# R2P_DCM_module.net
KiCad netlist of a schematic drawn in EAGLE
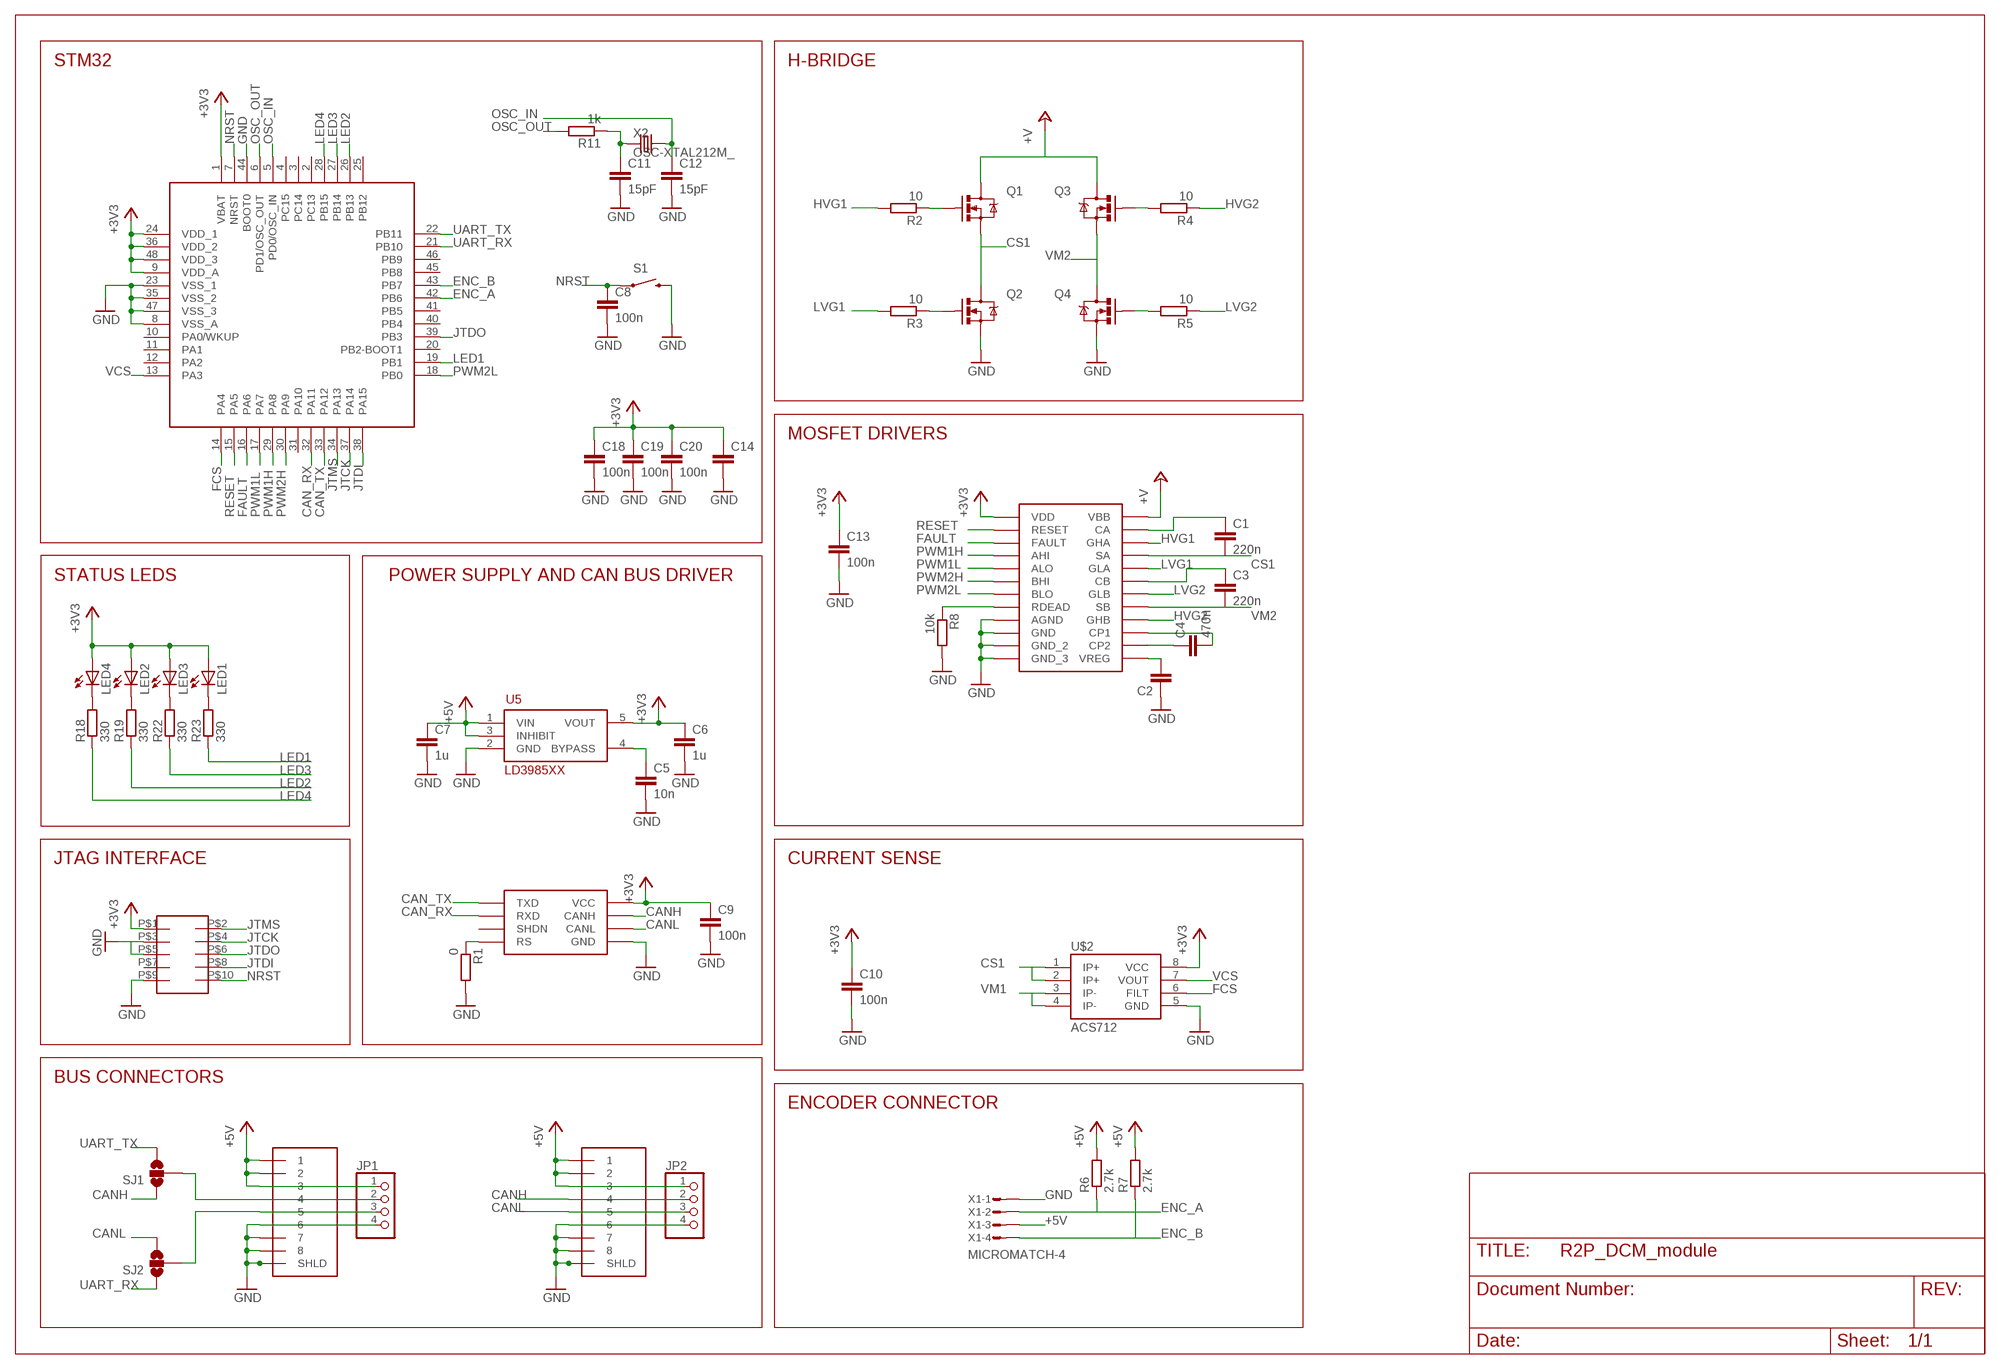
[diagram p0: schematic, sheet 1]

(export (version "E")
  (design (tool "Eeschema 10.0.6"))
  (components
    (comp (ref "1")
      (value "RJ45-43860")
      (footprint "eagle-import:0438600010")
      (libsource (lib "eagle-import") (part "RJ45-43860"))
    )
    (comp (ref "2")
      (value "RJ45-43860")
      (footprint "eagle-import:0438600010")
      (libsource (lib "eagle-import") (part "RJ45-43860"))
    )
    (comp (ref "C1")
      (value "220n")
      (footprint "eagle-import:C0603")
      (libsource (lib "eagle-import") (part "C-EUC0603"))
    )
    (comp (ref "C2")
      (value "C-EUC0805")
      (footprint "eagle-import:C0805")
      (libsource (lib "eagle-import") (part "C-EUC0805"))
    )
    (comp (ref "C3")
      (value "220n")
      (footprint "eagle-import:C0603")
      (libsource (lib "eagle-import") (part "C-EUC0603"))
    )
    (comp (ref "C4")
      (value "470n")
      (footprint "eagle-import:C0603")
      (libsource (lib "eagle-import") (part "C-EUC0603"))
    )
    (comp (ref "C5")
      (value "10n")
      (footprint "eagle-import:C0603")
      (libsource (lib "eagle-import") (part "C-EUC0603"))
    )
    (comp (ref "C6")
      (value "1u")
      (footprint "eagle-import:C0603")
      (libsource (lib "eagle-import") (part "C-EUC0603"))
    )
    (comp (ref "C7")
      (value "1u")
      (footprint "eagle-import:C0603")
      (libsource (lib "eagle-import") (part "C-EUC0603"))
    )
    (comp (ref "C8")
      (value "100n")
      (footprint "eagle-import:C0603")
      (libsource (lib "eagle-import") (part "C-EUC0603"))
    )
    (comp (ref "C9")
      (value "100n")
      (footprint "eagle-import:C0603")
      (libsource (lib "eagle-import") (part "C-EUC0603"))
    )
    (comp (ref "C10")
      (value "100n")
      (footprint "eagle-import:C0603")
      (libsource (lib "eagle-import") (part "C-EUC0603"))
    )
    (comp (ref "C11")
      (value "15pF")
      (footprint "eagle-import:C0603")
      (libsource (lib "eagle-import") (part "C-EUC0603"))
    )
    (comp (ref "C12")
      (value "15pF")
      (footprint "eagle-import:C0603")
      (libsource (lib "eagle-import") (part "C-EUC0603"))
    )
    (comp (ref "C13")
      (value "100n")
      (footprint "eagle-import:C0603")
      (libsource (lib "eagle-import") (part "C-EUC0603"))
    )
    (comp (ref "C14")
      (value "C-EUC0805")
      (footprint "eagle-import:C0805")
      (libsource (lib "eagle-import") (part "C-EUC0805"))
    )
    (comp (ref "C18")
      (value "100n")
      (footprint "eagle-import:C0603")
      (libsource (lib "eagle-import") (part "C-EUC0603"))
    )
    (comp (ref "C19")
      (value "100n")
      (footprint "eagle-import:C0603")
      (libsource (lib "eagle-import") (part "C-EUC0603"))
    )
    (comp (ref "C20")
      (value "100n")
      (footprint "eagle-import:C0603")
      (libsource (lib "eagle-import") (part "C-EUC0603"))
    )
    (comp (ref "JP1")
      (value "PINHD-1X4/90")
      (footprint "eagle-import:1X04_90")
      (libsource (lib "eagle-import") (part "PINHD-1X4/90"))
    )
    (comp (ref "JP2")
      (value "PINHD-1X4/90")
      (footprint "eagle-import:1X04_90")
      (libsource (lib "eagle-import") (part "PINHD-1X4/90"))
    )
    (comp (ref "LED1")
      (value "LEDCHIPLED_0805")
      (footprint "eagle-import:CHIPLED_0805")
      (libsource (lib "eagle-import") (part "LEDCHIPLED_0805"))
    )
    (comp (ref "LED2")
      (value "LEDCHIPLED_0805")
      (footprint "eagle-import:CHIPLED_0805")
      (libsource (lib "eagle-import") (part "LEDCHIPLED_0805"))
    )
    (comp (ref "LED3")
      (value "LEDCHIPLED_0805")
      (footprint "eagle-import:CHIPLED_0805")
      (libsource (lib "eagle-import") (part "LEDCHIPLED_0805"))
    )
    (comp (ref "LED4")
      (value "LEDCHIPLED_0805")
      (footprint "eagle-import:CHIPLED_0805")
      (libsource (lib "eagle-import") (part "LEDCHIPLED_0805"))
    )
    (comp (ref "Q1")
      (value "MOSFET-NCHANNELFDD8580")
      (footprint "eagle-import:DPAK")
      (libsource (lib "eagle-import") (part "MOSFET-NCHANNELFDD8580"))
    )
    (comp (ref "Q2")
      (value "MOSFET-NCHANNELFDD8580")
      (footprint "eagle-import:DPAK")
      (libsource (lib "eagle-import") (part "MOSFET-NCHANNELFDD8580"))
    )
    (comp (ref "Q3")
      (value "MOSFET-NCHANNELFDD8580")
      (footprint "eagle-import:DPAK")
      (libsource (lib "eagle-import") (part "MOSFET-NCHANNELFDD8580"))
    )
    (comp (ref "Q4")
      (value "MOSFET-NCHANNELFDD8580")
      (footprint "eagle-import:DPAK")
      (libsource (lib "eagle-import") (part "MOSFET-NCHANNELFDD8580"))
    )
    (comp (ref "R1")
      (value "0")
      (footprint "eagle-import:R0603")
      (libsource (lib "eagle-import") (part "R-EU_R0603"))
    )
    (comp (ref "R2")
      (value "10")
      (footprint "eagle-import:R0603")
      (libsource (lib "eagle-import") (part "R-EU_R0603"))
    )
    (comp (ref "R3")
      (value "10")
      (footprint "eagle-import:R0603")
      (libsource (lib "eagle-import") (part "R-EU_R0603"))
    )
    (comp (ref "R4")
      (value "10")
      (footprint "eagle-import:R0603")
      (libsource (lib "eagle-import") (part "R-EU_R0603"))
    )
    (comp (ref "R5")
      (value "10")
      (footprint "eagle-import:R0603")
      (libsource (lib "eagle-import") (part "R-EU_R0603"))
    )
    (comp (ref "R6")
      (value "2.7k")
      (footprint "eagle-import:R0603")
      (libsource (lib "eagle-import") (part "R-EU_R0603"))
    )
    (comp (ref "R7")
      (value "2.7k")
      (footprint "eagle-import:R0603")
      (libsource (lib "eagle-import") (part "R-EU_R0603"))
    )
    (comp (ref "R8")
      (value "10k")
      (footprint "eagle-import:R0603")
      (libsource (lib "eagle-import") (part "R-EU_R0603"))
    )
    (comp (ref "R11")
      (value "1k")
      (footprint "eagle-import:R0603")
      (libsource (lib "eagle-import") (part "R-EU_R0603"))
    )
    (comp (ref "R18")
      (value "330")
      (footprint "eagle-import:R0603")
      (libsource (lib "eagle-import") (part "R-EU_R0603"))
    )
    (comp (ref "R19")
      (value "330")
      (footprint "eagle-import:R0603")
      (libsource (lib "eagle-import") (part "R-EU_R0603"))
    )
    (comp (ref "R22")
      (value "330")
      (footprint "eagle-import:R0603")
      (libsource (lib "eagle-import") (part "R-EU_R0603"))
    )
    (comp (ref "R23")
      (value "330")
      (footprint "eagle-import:R0603")
      (libsource (lib "eagle-import") (part "R-EU_R0603"))
    )
    (comp (ref "S1")
      (value "SWITCH-MOMENTARY-2-SMD-1101NE")
      (footprint "eagle-import:TACTILE-SWITCH-1101NE")
      (libsource (lib "eagle-import") (part "SWITCH-MOMENTARY-2-SMD-1101NE"))
    )
    (comp (ref "SJ1")
      (value "SOLDERJUMPER_2WAYPASTE1&2")
      (footprint "eagle-import:SJ_3_PASTE1&2")
      (libsource (lib "eagle-import") (part "SOLDERJUMPER_2WAYPASTE1&2"))
    )
    (comp (ref "SJ2")
      (value "SOLDERJUMPER_2WAYPASTE1&2")
      (footprint "eagle-import:SJ_3_PASTE1&2")
      (libsource (lib "eagle-import") (part "SOLDERJUMPER_2WAYPASTE1&2"))
    )
    (comp (ref "SOT1")
      (value "MAX3051")
      (footprint "eagle-import:SOT23-8L")
      (libsource (lib "eagle-import") (part "MAX3051"))
    )
    (comp (ref "U$1")
      (value "A4940")
      (footprint "eagle-import:TSSOP24")
      (libsource (lib "eagle-import") (part "A4940"))
    )
    (comp (ref "U$2")
      (value "ACS712")
      (footprint "eagle-import:SO08")
      (libsource (lib "eagle-import") (part "ACS712"))
    )
    (comp (ref "U$4")
      (value "FTSH-105")
      (footprint "eagle-import:FTSH-105")
      (libsource (lib "eagle-import") (part "FTSH-105"))
    )
    (comp (ref "U1")
      (value "STM32F103CX")
      (footprint "eagle-import:LQFP48")
      (libsource (lib "eagle-import") (part "STM32F103CX"))
    )
    (comp (ref "U5")
      (value "LD3985XX")
      (footprint "eagle-import:SOT23-5L")
      (libsource (lib "eagle-import") (part "LD3985XX"))
    )
    (comp (ref "X1")
      (value "MICROMATCH-4")
      (footprint "eagle-import:MICROMATCH-4")
      (libsource (lib "eagle-import") (part "MICROMATCH-4"))
    )
    (comp (ref "X2")
      (value "OSC-XTAL212M_")
      (footprint "eagle-import:4X6")
      (libsource (lib "eagle-import") (part "OSC-XTAL212M_"))
    )
  )
  (nets
    (net (code "1") (name "+3V3") (class "Default")
      (node (ref "C10") (pin "1") (pinfunction "1_1") (pintype "passive"))
      (node (ref "C13") (pin "1") (pinfunction "1_1") (pintype "passive"))
      (node (ref "C14") (pin "1") (pinfunction "1_1") (pintype "passive"))
      (node (ref "C18") (pin "1") (pinfunction "1_1") (pintype "passive"))
      (node (ref "C19") (pin "1") (pinfunction "1_1") (pintype "passive"))
      (node (ref "C20") (pin "1") (pinfunction "1_1") (pintype "passive"))
      (node (ref "C6") (pin "1") (pinfunction "1_1") (pintype "passive"))
      (node (ref "C9") (pin "1") (pinfunction "1_1") (pintype "passive"))
      (node (ref "LED1") (pin "A") (pinfunction "A_A") (pintype "passive"))
      (node (ref "LED2") (pin "A") (pinfunction "A_A") (pintype "passive"))
      (node (ref "LED3") (pin "A") (pinfunction "A_A") (pintype "passive"))
      (node (ref "LED4") (pin "A") (pinfunction "A_A") (pintype "passive"))
      (node (ref "SOT1") (pin "P$3") (pinfunction "VCC_P$3") (pintype "bidirectional"))
      (node (ref "U$1") (pin "21") (pinfunction "VDD_21") (pintype "bidirectional"))
      (node (ref "U$2") (pin "8") (pinfunction "VCC_8") (pintype "bidirectional"))
      (node (ref "U$4") (pin "P$1") (pinfunction "P$1_P$1") (pintype "bidirectional"))
      (node (ref "U1") (pin "1") (pinfunction "VBAT_1") (pintype "bidirectional"))
      (node (ref "U1") (pin "24") (pinfunction "VDD_1_24") (pintype "bidirectional"))
      (node (ref "U1") (pin "36") (pinfunction "VDD_2_36") (pintype "bidirectional"))
      (node (ref "U1") (pin "48") (pinfunction "VDD_3_48") (pintype "bidirectional"))
      (node (ref "U1") (pin "9") (pinfunction "VDD_A_9") (pintype "bidirectional"))
      (node (ref "U5") (pin "5") (pinfunction "VOUT_5") (pintype "bidirectional"))
    )
    (net (code "2") (name "+5V") (class "Default")
      (node (ref "1") (pin "P$1") (pinfunction "1_P$1") (pintype "bidirectional"))
      (node (ref "1") (pin "P$2") (pinfunction "2_P$2") (pintype "bidirectional"))
      (node (ref "1") (pin "P$3") (pinfunction "3_P$3") (pintype "bidirectional"))
      (node (ref "2") (pin "P$1") (pinfunction "1_P$1") (pintype "bidirectional"))
      (node (ref "2") (pin "P$2") (pinfunction "2_P$2") (pintype "bidirectional"))
      (node (ref "2") (pin "P$3") (pinfunction "3_P$3") (pintype "bidirectional"))
      (node (ref "C7") (pin "1") (pinfunction "1_1") (pintype "passive"))
      (node (ref "JP1") (pin "1") (pinfunction "1_1") (pintype "passive"))
      (node (ref "JP2") (pin "1") (pinfunction "1_1") (pintype "passive"))
      (node (ref "R6") (pin "2") (pinfunction "2_2") (pintype "passive"))
      (node (ref "R7") (pin "2") (pinfunction "2_2") (pintype "passive"))
      (node (ref "U5") (pin "1") (pinfunction "VIN_1") (pintype "bidirectional"))
      (node (ref "U5") (pin "3") (pinfunction "INHIBIT_3") (pintype "bidirectional"))
      (node (ref "X1") (pin "3") (pinfunction "S_3") (pintype "passive"))
    )
    (net (code "3") (name "+V") (class "Default")
      (node (ref "Q1") (pin "4") (pinfunction "D_4") (pintype "passive"))
      (node (ref "Q3") (pin "4") (pinfunction "D_4") (pintype "passive"))
      (node (ref "U$1") (pin "12") (pinfunction "VBB_12") (pintype "bidirectional"))
    )
    (net (code "4") (name "/CANH") (class "Default")
      (node (ref "2") (pin "P$4") (pinfunction "4_P$4") (pintype "bidirectional"))
      (node (ref "JP2") (pin "2") (pinfunction "2_2") (pintype "passive"))
      (node (ref "SJ1") (pin "1") (pinfunction "1_1") (pintype "passive"))
      (node (ref "SOT1") (pin "P$7") (pinfunction "CANH_P$7") (pintype "bidirectional"))
    )
    (net (code "5") (name "/CANL") (class "Default")
      (node (ref "2") (pin "P$5") (pinfunction "5_P$5") (pintype "bidirectional"))
      (node (ref "JP2") (pin "3") (pinfunction "3_3") (pintype "passive"))
      (node (ref "SJ2") (pin "3") (pinfunction "3_3") (pintype "passive"))
      (node (ref "SOT1") (pin "P$6") (pinfunction "CANL_P$6") (pintype "bidirectional"))
    )
    (net (code "6") (name "/CAN_RX") (class "Default")
      (node (ref "SOT1") (pin "P$4") (pinfunction "RXD_P$4") (pintype "bidirectional"))
      (node (ref "U1") (pin "32") (pinfunction "PA11_32") (pintype "bidirectional"))
    )
    (net (code "7") (name "/CAN_TX") (class "Default")
      (node (ref "SOT1") (pin "P$1") (pinfunction "TXD_P$1") (pintype "bidirectional"))
      (node (ref "U1") (pin "33") (pinfunction "PA12_33") (pintype "bidirectional"))
    )
    (net (code "8") (name "/CS1") (class "Default")
      (node (ref "C1") (pin "2") (pinfunction "2_2") (pintype "passive"))
      (node (ref "Q1") (pin "3") (pinfunction "S_3") (pintype "passive"))
      (node (ref "Q2") (pin "4") (pinfunction "D_4") (pintype "passive"))
      (node (ref "U$1") (pin "10") (pinfunction "SA_10") (pintype "bidirectional"))
      (node (ref "U$2") (pin "1") (pinfunction "IP+_1") (pintype "bidirectional"))
      (node (ref "U$2") (pin "2") (pinfunction "IP+_2") (pintype "bidirectional"))
    )
    (net (code "9") (name "/ENC_A") (class "Default")
      (node (ref "R6") (pin "1") (pinfunction "1_1") (pintype "passive"))
      (node (ref "U1") (pin "42") (pinfunction "PB6_42") (pintype "bidirectional"))
      (node (ref "X1") (pin "2") (pinfunction "S_2") (pintype "passive"))
    )
    (net (code "10") (name "/ENC_B") (class "Default")
      (node (ref "R7") (pin "1") (pinfunction "1_1") (pintype "passive"))
      (node (ref "U1") (pin "43") (pinfunction "PB7_43") (pintype "bidirectional"))
      (node (ref "X1") (pin "4") (pinfunction "S_4") (pintype "passive"))
    )
    (net (code "11") (name "/FAULT") (class "Default")
      (node (ref "U$1") (pin "24") (pinfunction "FAULT_24") (pintype "bidirectional"))
      (node (ref "U1") (pin "16") (pinfunction "PA6_16") (pintype "bidirectional"))
    )
    (net (code "12") (name "/FCS") (class "Default")
      (node (ref "U$2") (pin "6") (pinfunction "FILT_6") (pintype "bidirectional"))
      (node (ref "U1") (pin "14") (pinfunction "PA4_14") (pintype "bidirectional"))
    )
    (net (code "13") (name "/HVG1") (class "Default")
      (node (ref "R2") (pin "2") (pinfunction "2_2") (pintype "passive"))
      (node (ref "U$1") (pin "9") (pinfunction "GHA_9") (pintype "bidirectional"))
    )
    (net (code "14") (name "/HVG2") (class "Default")
      (node (ref "R4") (pin "1") (pinfunction "1_1") (pintype "passive"))
      (node (ref "U$1") (pin "5") (pinfunction "GHB_5") (pintype "bidirectional"))
    )
    (net (code "15") (name "/JTCK") (class "Default")
      (node (ref "U$4") (pin "P$4") (pinfunction "P$4_P$4") (pintype "bidirectional"))
      (node (ref "U1") (pin "37") (pinfunction "PA14_37") (pintype "bidirectional"))
    )
    (net (code "16") (name "/JTDI") (class "Default")
      (node (ref "U$4") (pin "P$8") (pinfunction "P$8_P$8") (pintype "bidirectional"))
      (node (ref "U1") (pin "38") (pinfunction "PA15_38") (pintype "bidirectional"))
    )
    (net (code "17") (name "/JTDO") (class "Default")
      (node (ref "U$4") (pin "P$6") (pinfunction "P$6_P$6") (pintype "bidirectional"))
      (node (ref "U1") (pin "39") (pinfunction "PB3_39") (pintype "bidirectional"))
    )
    (net (code "18") (name "/JTMS") (class "Default")
      (node (ref "U$4") (pin "P$2") (pinfunction "P$2_P$2") (pintype "bidirectional"))
      (node (ref "U1") (pin "34") (pinfunction "PA13_34") (pintype "bidirectional"))
    )
    (net (code "19") (name "/LED1") (class "Default")
      (node (ref "R23") (pin "1") (pinfunction "1_1") (pintype "passive"))
      (node (ref "U1") (pin "19") (pinfunction "PB1_19") (pintype "bidirectional"))
    )
    (net (code "20") (name "/LED2") (class "Default")
      (node (ref "R19") (pin "1") (pinfunction "1_1") (pintype "passive"))
      (node (ref "U1") (pin "26") (pinfunction "PB13_26") (pintype "bidirectional"))
    )
    (net (code "21") (name "/LED3") (class "Default")
      (node (ref "R22") (pin "1") (pinfunction "1_1") (pintype "passive"))
      (node (ref "U1") (pin "27") (pinfunction "PB14_27") (pintype "bidirectional"))
    )
    (net (code "22") (name "/LED4") (class "Default")
      (node (ref "R18") (pin "1") (pinfunction "1_1") (pintype "passive"))
      (node (ref "U1") (pin "28") (pinfunction "PB15_28") (pintype "bidirectional"))
    )
    (net (code "23") (name "/LVG1") (class "Default")
      (node (ref "R3") (pin "2") (pinfunction "2_2") (pintype "passive"))
      (node (ref "U$1") (pin "11") (pinfunction "GLA_11") (pintype "bidirectional"))
    )
    (net (code "24") (name "/LVG2") (class "Default")
      (node (ref "R5") (pin "1") (pinfunction "1_1") (pintype "passive"))
      (node (ref "U$1") (pin "3") (pinfunction "GLB_3") (pintype "bidirectional"))
    )
    (net (code "25") (name "/NRST") (class "Default")
      (node (ref "C8") (pin "1") (pinfunction "1_1") (pintype "passive"))
      (node (ref "S1") (pin "P$1") (pinfunction "1_P$1") (pintype "passive"))
      (node (ref "U$4") (pin "P$10") (pinfunction "P$10_P$10") (pintype "bidirectional"))
      (node (ref "U1") (pin "7") (pinfunction "NRST_7") (pintype "bidirectional"))
    )
    (net (code "26") (name "/OSC_IN") (class "Default")
      (node (ref "C12") (pin "1") (pinfunction "1_1") (pintype "passive"))
      (node (ref "U1") (pin "5") (pinfunction "PD0/OSC_IN_5") (pintype "bidirectional"))
      (node (ref "X2") (pin "2") (pinfunction "X2_2") (pintype "bidirectional"))
    )
    (net (code "27") (name "/OSC_OUT") (class "Default")
      (node (ref "R11") (pin "2") (pinfunction "2_2") (pintype "passive"))
      (node (ref "U1") (pin "6") (pinfunction "PD1/OSC_OUT_6") (pintype "bidirectional"))
    )
    (net (code "28") (name "/PWM1H") (class "Default")
      (node (ref "U$1") (pin "20") (pinfunction "AHI_20") (pintype "bidirectional"))
      (node (ref "U1") (pin "29") (pinfunction "PA8_29") (pintype "bidirectional"))
    )
    (net (code "29") (name "/PWM1L") (class "Default")
      (node (ref "U$1") (pin "19") (pinfunction "ALO_19") (pintype "bidirectional"))
      (node (ref "U1") (pin "17") (pinfunction "PA7_17") (pintype "bidirectional"))
    )
    (net (code "30") (name "/PWM2H") (class "Default")
      (node (ref "U$1") (pin "18") (pinfunction "BHI_18") (pintype "bidirectional"))
      (node (ref "U1") (pin "30") (pinfunction "PA9_30") (pintype "bidirectional"))
    )
    (net (code "31") (name "/PWM2L") (class "Default")
      (node (ref "U$1") (pin "17") (pinfunction "BLO_17") (pintype "bidirectional"))
      (node (ref "U1") (pin "18") (pinfunction "PB0_18") (pintype "bidirectional"))
    )
    (net (code "32") (name "/RESET") (class "Default")
      (node (ref "U$1") (pin "1") (pinfunction "RESET_1") (pintype "bidirectional"))
      (node (ref "U1") (pin "15") (pinfunction "PA5_15") (pintype "bidirectional"))
    )
    (net (code "33") (name "/UART_RX") (class "Default")
      (node (ref "SJ2") (pin "1") (pinfunction "1_1") (pintype "passive"))
      (node (ref "U1") (pin "21") (pinfunction "PB10_21") (pintype "bidirectional"))
    )
    (net (code "34") (name "/UART_TX") (class "Default")
      (node (ref "SJ1") (pin "3") (pinfunction "3_3") (pintype "passive"))
      (node (ref "U1") (pin "22") (pinfunction "PB11_22") (pintype "bidirectional"))
    )
    (net (code "35") (name "/VCS") (class "Default")
      (node (ref "U$2") (pin "7") (pinfunction "VOUT_7") (pintype "bidirectional"))
      (node (ref "U1") (pin "13") (pinfunction "PA3_13") (pintype "bidirectional"))
    )
    (net (code "36") (name "/VM1") (class "Default")
      (node (ref "U$2") (pin "3") (pinfunction "IP-_3") (pintype "bidirectional"))
      (node (ref "U$2") (pin "4") (pinfunction "IP-_4") (pintype "bidirectional"))
    )
    (net (code "37") (name "/VM2") (class "Default")
      (node (ref "C3") (pin "2") (pinfunction "2_2") (pintype "passive"))
      (node (ref "Q3") (pin "3") (pinfunction "S_3") (pintype "passive"))
      (node (ref "Q4") (pin "4") (pinfunction "D_4") (pintype "passive"))
      (node (ref "U$1") (pin "4") (pinfunction "SB_4") (pintype "bidirectional"))
    )
    (net (code "38") (name "GND") (class "Default")
      (node (ref "1") (pin "P$10") (pinfunction "P$1_P$10") (pintype "power_in"))
      (node (ref "1") (pin "P$6") (pinfunction "6_P$6") (pintype "bidirectional"))
      (node (ref "1") (pin "P$7") (pinfunction "7_P$7") (pintype "bidirectional"))
      (node (ref "1") (pin "P$8") (pinfunction "8_P$8") (pintype "bidirectional"))
      (node (ref "1") (pin "P$9") (pinfunction "SHLD_P$9") (pintype "power_in"))
      (node (ref "2") (pin "P$10") (pinfunction "P$1_P$10") (pintype "power_in"))
      (node (ref "2") (pin "P$6") (pinfunction "6_P$6") (pintype "bidirectional"))
      (node (ref "2") (pin "P$7") (pinfunction "7_P$7") (pintype "bidirectional"))
      (node (ref "2") (pin "P$8") (pinfunction "8_P$8") (pintype "bidirectional"))
      (node (ref "2") (pin "P$9") (pinfunction "SHLD_P$9") (pintype "power_in"))
      (node (ref "C10") (pin "2") (pinfunction "2_2") (pintype "passive"))
      (node (ref "C11") (pin "2") (pinfunction "2_2") (pintype "passive"))
      (node (ref "C12") (pin "2") (pinfunction "2_2") (pintype "passive"))
      (node (ref "C13") (pin "2") (pinfunction "2_2") (pintype "passive"))
      (node (ref "C14") (pin "2") (pinfunction "2_2") (pintype "passive"))
      (node (ref "C18") (pin "2") (pinfunction "2_2") (pintype "passive"))
      (node (ref "C19") (pin "2") (pinfunction "2_2") (pintype "passive"))
      (node (ref "C2") (pin "1") (pinfunction "1_1") (pintype "passive"))
      (node (ref "C20") (pin "2") (pinfunction "2_2") (pintype "passive"))
      (node (ref "C5") (pin "2") (pinfunction "2_2") (pintype "passive"))
      (node (ref "C6") (pin "2") (pinfunction "2_2") (pintype "passive"))
      (node (ref "C7") (pin "2") (pinfunction "2_2") (pintype "passive"))
      (node (ref "C8") (pin "2") (pinfunction "2_2") (pintype "passive"))
      (node (ref "C9") (pin "2") (pinfunction "2_2") (pintype "passive"))
      (node (ref "JP1") (pin "4") (pinfunction "4_4") (pintype "passive"))
      (node (ref "JP2") (pin "4") (pinfunction "4_4") (pintype "passive"))
      (node (ref "Q2") (pin "3") (pinfunction "S_3") (pintype "passive"))
      (node (ref "Q4") (pin "3") (pinfunction "S_3") (pintype "passive"))
      (node (ref "R1") (pin "2") (pinfunction "2_2") (pintype "passive"))
      (node (ref "R8") (pin "2") (pinfunction "2_2") (pintype "passive"))
      (node (ref "S1") (pin "P$2") (pinfunction "2_P$2") (pintype "passive"))
      (node (ref "SOT1") (pin "P$2") (pinfunction "GND_P$2") (pintype "bidirectional"))
      (node (ref "U$1") (pin "15") (pinfunction "GND_2_15") (pintype "bidirectional"))
      (node (ref "U$1") (pin "16") (pinfunction "GND_3_16") (pintype "bidirectional"))
      (node (ref "U$1") (pin "2") (pinfunction "GND_2") (pintype "bidirectional"))
      (node (ref "U$1") (pin "22") (pinfunction "AGND_22") (pintype "bidirectional"))
      (node (ref "U$1") (pin "PAD") (pinfunction "GND_PAD") (pintype "bidirectional"))
      (node (ref "U$2") (pin "5") (pinfunction "GND_5") (pintype "bidirectional"))
      (node (ref "U$4") (pin "P$3") (pinfunction "P$3_P$3") (pintype "bidirectional"))
      (node (ref "U$4") (pin "P$9") (pinfunction "P$9_P$9") (pintype "bidirectional"))
      (node (ref "U1") (pin "23") (pinfunction "VSS_1_23") (pintype "bidirectional"))
      (node (ref "U1") (pin "35") (pinfunction "VSS_2_35") (pintype "bidirectional"))
      (node (ref "U1") (pin "44") (pinfunction "BOOT0_44") (pintype "bidirectional"))
      (node (ref "U1") (pin "47") (pinfunction "VSS_3_47") (pintype "bidirectional"))
      (node (ref "U1") (pin "8") (pinfunction "VSS_A_8") (pintype "bidirectional"))
      (node (ref "U5") (pin "2") (pinfunction "GND_2") (pintype "bidirectional"))
      (node (ref "X1") (pin "1") (pinfunction "S_1") (pintype "passive"))
    )
    (net (code "39") (name "Net-(1-4)") (class "Default")
      (node (ref "1") (pin "P$4") (pinfunction "4_P$4") (pintype "bidirectional"))
      (node (ref "JP1") (pin "2") (pinfunction "2_2") (pintype "passive"))
      (node (ref "SJ1") (pin "2") (pinfunction "2_2") (pintype "passive"))
    )
    (net (code "40") (name "Net-(1-5)") (class "Default")
      (node (ref "1") (pin "P$5") (pinfunction "5_P$5") (pintype "bidirectional"))
      (node (ref "JP1") (pin "3") (pinfunction "3_3") (pintype "passive"))
      (node (ref "SJ2") (pin "2") (pinfunction "2_2") (pintype "passive"))
    )
    (net (code "41") (name "Net-(LED1-PadC)") (class "Default")
      (node (ref "LED1") (pin "C") (pinfunction "C_C") (pintype "passive"))
      (node (ref "R23") (pin "2") (pinfunction "2_2") (pintype "passive"))
    )
    (net (code "42") (name "Net-(LED2-PadC)") (class "Default")
      (node (ref "LED2") (pin "C") (pinfunction "C_C") (pintype "passive"))
      (node (ref "R19") (pin "2") (pinfunction "2_2") (pintype "passive"))
    )
    (net (code "43") (name "Net-(LED3-PadC)") (class "Default")
      (node (ref "LED3") (pin "C") (pinfunction "C_C") (pintype "passive"))
      (node (ref "R22") (pin "2") (pinfunction "2_2") (pintype "passive"))
    )
    (net (code "44") (name "Net-(LED4-PadC)") (class "Default")
      (node (ref "LED4") (pin "C") (pinfunction "C_C") (pintype "passive"))
      (node (ref "R18") (pin "2") (pinfunction "2_2") (pintype "passive"))
    )
    (net (code "45") (name "Net-(Q1-G)") (class "Default")
      (node (ref "Q1") (pin "1") (pinfunction "G_1") (pintype "passive"))
      (node (ref "R2") (pin "1") (pinfunction "1_1") (pintype "passive"))
    )
    (net (code "46") (name "Net-(Q2-G)") (class "Default")
      (node (ref "Q2") (pin "1") (pinfunction "G_1") (pintype "passive"))
      (node (ref "R3") (pin "1") (pinfunction "1_1") (pintype "passive"))
    )
    (net (code "47") (name "Net-(Q3-G)") (class "Default")
      (node (ref "Q3") (pin "1") (pinfunction "G_1") (pintype "passive"))
      (node (ref "R4") (pin "2") (pinfunction "2_2") (pintype "passive"))
    )
    (net (code "48") (name "Net-(Q4-G)") (class "Default")
      (node (ref "Q4") (pin "1") (pinfunction "G_1") (pintype "passive"))
      (node (ref "R5") (pin "2") (pinfunction "2_2") (pintype "passive"))
    )
    (net (code "49") (name "Net-(SOT1-RS)") (class "Default")
      (node (ref "R1") (pin "1") (pinfunction "1_1") (pintype "passive"))
      (node (ref "SOT1") (pin "P$8") (pinfunction "RS_P$8") (pintype "bidirectional"))
    )
    (net (code "50") (name "Net-(U$1-CA)") (class "Default")
      (node (ref "C1") (pin "1") (pinfunction "1_1") (pintype "passive"))
      (node (ref "U$1") (pin "8") (pinfunction "CA_8") (pintype "bidirectional"))
    )
    (net (code "51") (name "Net-(U$1-CB)") (class "Default")
      (node (ref "C3") (pin "1") (pinfunction "1_1") (pintype "passive"))
      (node (ref "U$1") (pin "6") (pinfunction "CB_6") (pintype "bidirectional"))
    )
    (net (code "52") (name "Net-(U$1-CP1)") (class "Default")
      (node (ref "C4") (pin "2") (pinfunction "2_2") (pintype "passive"))
      (node (ref "U$1") (pin "14") (pinfunction "CP1_14") (pintype "bidirectional"))
    )
    (net (code "53") (name "Net-(U$1-CP2)") (class "Default")
      (node (ref "C4") (pin "1") (pinfunction "1_1") (pintype "passive"))
      (node (ref "U$1") (pin "13") (pinfunction "CP2_13") (pintype "bidirectional"))
    )
    (net (code "54") (name "Net-(U$1-RDEAD)") (class "Default")
      (node (ref "R8") (pin "1") (pinfunction "1_1") (pintype "passive"))
      (node (ref "U$1") (pin "23") (pinfunction "RDEAD_23") (pintype "bidirectional"))
    )
    (net (code "55") (name "Net-(U$1-VREG)") (class "Default")
      (node (ref "C2") (pin "2") (pinfunction "2_2") (pintype "passive"))
      (node (ref "U$1") (pin "7") (pinfunction "VREG_7") (pintype "bidirectional"))
    )
    (net (code "56") (name "Net-(U5-BYPASS)") (class "Default")
      (node (ref "C5") (pin "1") (pinfunction "1_1") (pintype "passive"))
      (node (ref "U5") (pin "4") (pinfunction "BYPASS_4") (pintype "bidirectional"))
    )
    (net (code "57") (name "Net-(X2-X1)") (class "Default")
      (node (ref "C11") (pin "1") (pinfunction "1_1") (pintype "passive"))
      (node (ref "R11") (pin "1") (pinfunction "1_1") (pintype "passive"))
      (node (ref "X2") (pin "1") (pinfunction "X1_1") (pintype "bidirectional"))
    )
    (net (code "58") (name "unconnected-(SOT1-SHDN-PadP$5)") (class "Default")
      (node (ref "SOT1") (pin "P$5") (pinfunction "SHDN_P$5") (pintype "bidirectional"))
    )
    (net (code "59") (name "unconnected-(U$4-PadP$5)") (class "Default")
      (node (ref "U$4") (pin "P$5") (pinfunction "P$5_P$5") (pintype "bidirectional"))
    )
    (net (code "60") (name "unconnected-(U$4-PadP$7)") (class "Default")
      (node (ref "U$4") (pin "P$7") (pinfunction "P$7_P$7") (pintype "bidirectional"))
    )
    (net (code "61") (name "unconnected-(U1-PA0{slash}WKUP-Pad10)") (class "Default")
      (node (ref "U1") (pin "10") (pinfunction "PA0/WKUP_10") (pintype "bidirectional"))
    )
    (net (code "62") (name "unconnected-(U1-PA1-Pad11)") (class "Default")
      (node (ref "U1") (pin "11") (pinfunction "PA1_11") (pintype "bidirectional"))
    )
    (net (code "63") (name "unconnected-(U1-PA2-Pad12)") (class "Default")
      (node (ref "U1") (pin "12") (pinfunction "PA2_12") (pintype "bidirectional"))
    )
    (net (code "64") (name "unconnected-(U1-PA10-Pad31)") (class "Default")
      (node (ref "U1") (pin "31") (pinfunction "PA10_31") (pintype "bidirectional"))
    )
    (net (code "65") (name "unconnected-(U1-PB2-BOOT1-Pad20)") (class "Default")
      (node (ref "U1") (pin "20") (pinfunction "PB2-BOOT1_20") (pintype "bidirectional"))
    )
    (net (code "66") (name "unconnected-(U1-PB4-Pad40)") (class "Default")
      (node (ref "U1") (pin "40") (pinfunction "PB4_40") (pintype "bidirectional"))
    )
    (net (code "67") (name "unconnected-(U1-PB5-Pad41)") (class "Default")
      (node (ref "U1") (pin "41") (pinfunction "PB5_41") (pintype "bidirectional"))
    )
    (net (code "68") (name "unconnected-(U1-PB8-Pad45)") (class "Default")
      (node (ref "U1") (pin "45") (pinfunction "PB8_45") (pintype "bidirectional"))
    )
    (net (code "69") (name "unconnected-(U1-PB9-Pad46)") (class "Default")
      (node (ref "U1") (pin "46") (pinfunction "PB9_46") (pintype "bidirectional"))
    )
    (net (code "70") (name "unconnected-(U1-PB12-Pad25)") (class "Default")
      (node (ref "U1") (pin "25") (pinfunction "PB12_25") (pintype "bidirectional"))
    )
    (net (code "71") (name "unconnected-(U1-PC13-Pad2)") (class "Default")
      (node (ref "U1") (pin "2") (pinfunction "PC13_2") (pintype "bidirectional"))
    )
    (net (code "72") (name "unconnected-(U1-PC14-Pad3)") (class "Default")
      (node (ref "U1") (pin "3") (pinfunction "PC14_3") (pintype "bidirectional"))
    )
    (net (code "73") (name "unconnected-(U1-PC15-Pad4)") (class "Default")
      (node (ref "U1") (pin "4") (pinfunction "PC15_4") (pintype "bidirectional"))
    )
  )
)
